# 3_6.net
KiCad netlist of a schematic drawn in Altium Designer
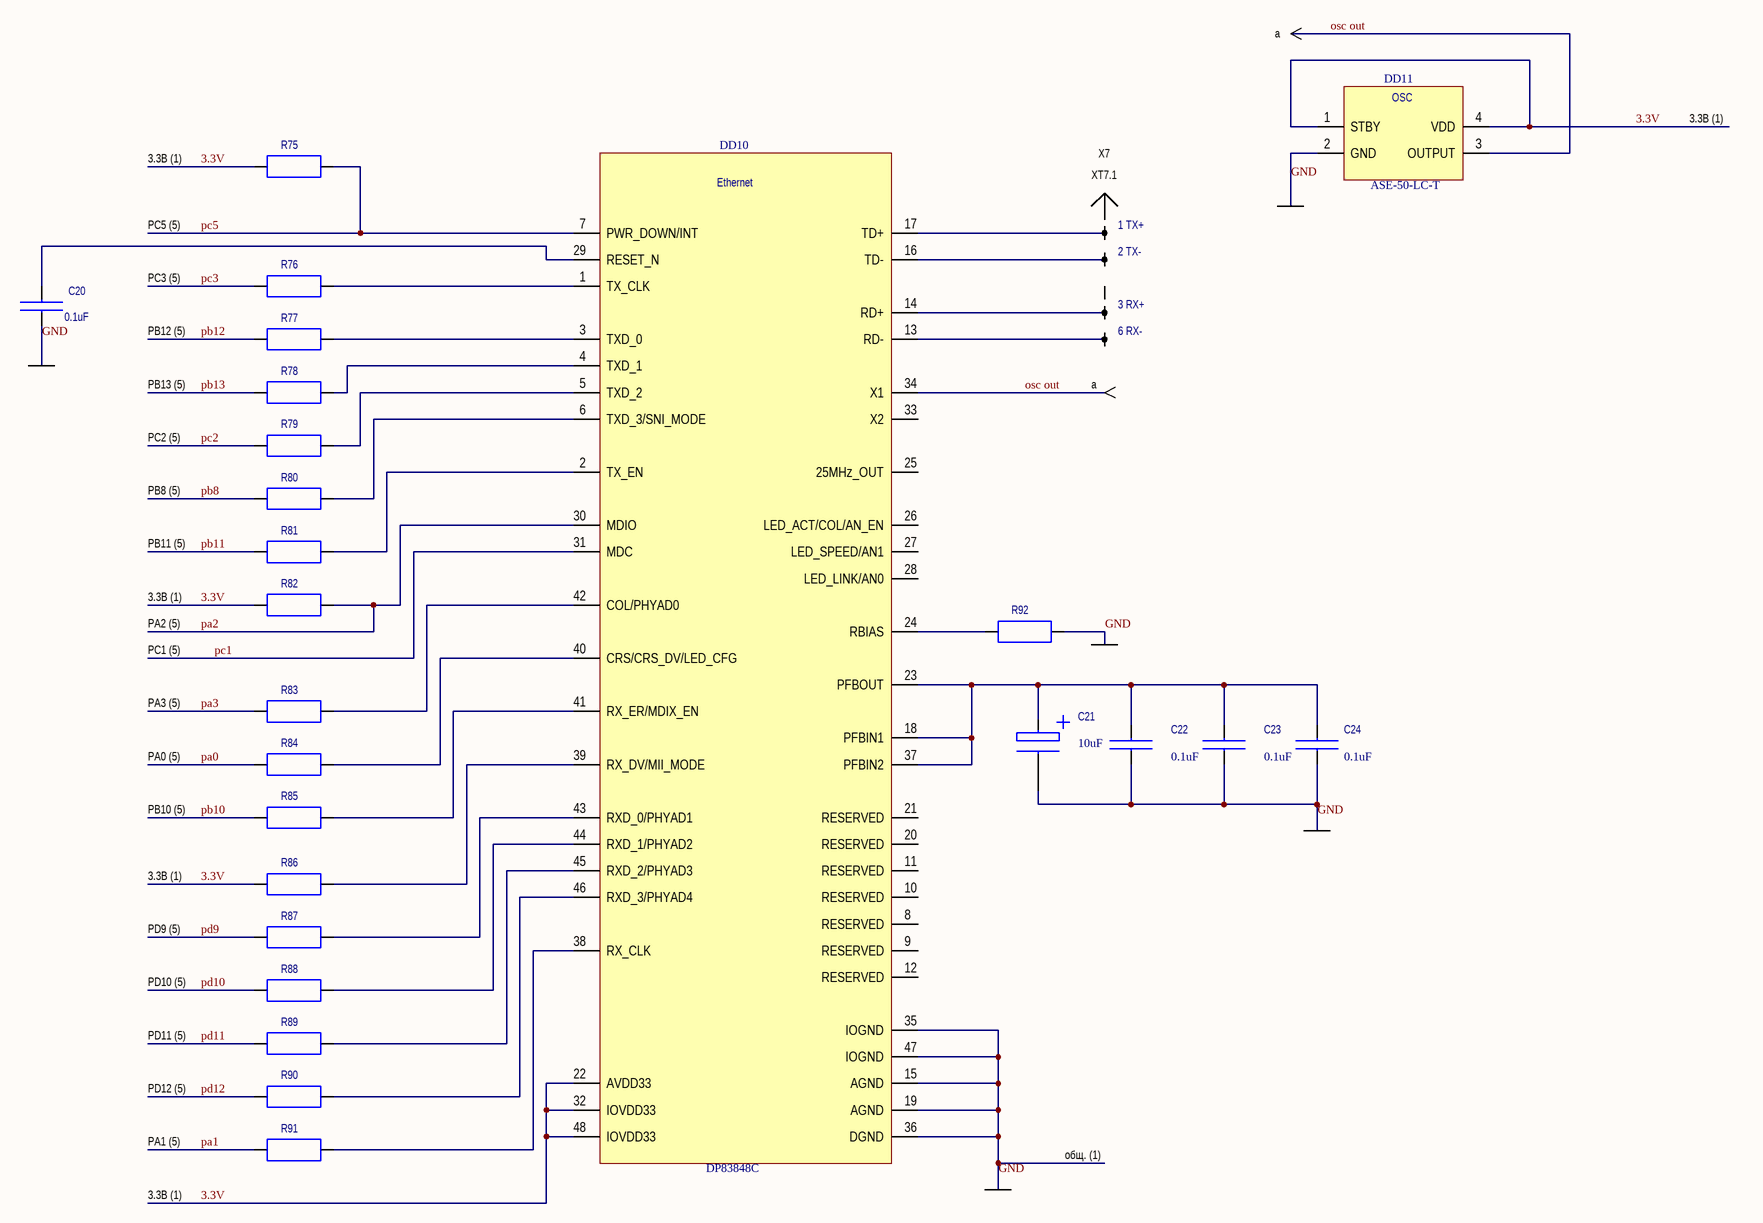
[diagram p0: Э3_6.SchDoc]

(export (version "E")
  (design (tool "Eeschema 10.0.6"))
  (components
    (comp (ref "C20") (value "0.1uF") (footprint "PcbLib1:CAP0805") (libsource (lib "Schlib1") (part "C")))
    (comp (ref "C21") (value "10uF") (footprint "PcbLib1:CAPT") (libsource (lib "Schlib1") (part "CL")))
    (comp (ref "C22") (value "0.1uF") (footprint "PcbLib1:CAP0805") (libsource (lib "Schlib1") (part "C")))
    (comp (ref "C23") (value "0.1uF") (libsource (lib "Schlib1") (part "C_2")))
    (comp (ref "C24") (value "0.1uF") (libsource (lib "Schlib1") (part "C_2")))
    (comp (ref "DD10")
      (value "DP83848C")
      (footprint "PcbLib1:VBH48A_N")
      (libsource (lib "Schlib1") (part "DP83848C"))
    )
    (comp (ref "DD11")
      (value "ASE-50-LC-T")
      (footprint "PcbLib1:ASE_OSC")
      (libsource (lib "Schlib1") (part "ASE-50-LC-T"))
    )
    (comp (ref "R75") (value "2.2k") (footprint "PcbLib1:RES0805") (libsource (lib "Schlib1") (part "R")))
    (comp (ref "R76") (value "51") (footprint "PcbLib1:RES0805") (libsource (lib "Schlib1") (part "R")))
    (comp (ref "R77") (value "51") (footprint "PcbLib1:RES0805") (libsource (lib "Schlib1") (part "R")))
    (comp (ref "R78") (value "51") (footprint "PcbLib1:RES0805") (libsource (lib "Schlib1") (part "R")))
    (comp (ref "R79") (value "51") (footprint "PcbLib1:RES0805") (libsource (lib "Schlib1") (part "R")))
    (comp (ref "R80") (value "51") (footprint "PcbLib1:RES0805") (libsource (lib "Schlib1") (part "R")))
    (comp (ref "R81") (value "51") (footprint "PcbLib1:RES0805") (libsource (lib "Schlib1") (part "R")))
    (comp (ref "R82") (value "1.5k") (footprint "PcbLib1:RES0805") (libsource (lib "Schlib1") (part "R")))
    (comp (ref "R83") (value "51") (footprint "PcbLib1:RES0805") (libsource (lib "Schlib1") (part "R")))
    (comp (ref "R84") (value "51") (footprint "PcbLib1:RES0805") (libsource (lib "Schlib1") (part "R")))
    (comp (ref "R85") (value "51") (footprint "PcbLib1:RES0805") (libsource (lib "Schlib1") (part "R")))
    (comp (ref "R86") (value "2.2k") (footprint "PcbLib1:RES0805") (libsource (lib "Schlib1") (part "R")))
    (comp (ref "R87") (value "51") (footprint "PcbLib1:RES0805") (libsource (lib "Schlib1") (part "R")))
    (comp (ref "R88") (value "51") (footprint "PcbLib1:RES0805") (libsource (lib "Schlib1") (part "R")))
    (comp (ref "R89") (value "51") (footprint "PcbLib1:RES0805") (libsource (lib "Schlib1") (part "R")))
    (comp (ref "R90") (value "51") (footprint "PcbLib1:RES0805") (libsource (lib "Schlib1") (part "R")))
    (comp (ref "R91") (value "51") (footprint "PcbLib1:RES0805") (libsource (lib "Schlib1") (part "R")))
    (comp (ref "R92") (value "4.87k") (libsource (lib "Schlib1") (part "R_1")))
    (comp (ref "X7") (value "1 TX+") (footprint "PcbLib1:RJ45") (libsource (lib "Schlib1") (part "RJ45")))
  )
  (nets
    (net (code "1") (name "/3.3V") (class "Default")
      (node (ref "DD10") (pin "22") (pinfunction "AVDD33_22") (pintype "passive"))
      (node (ref "DD10") (pin "32") (pinfunction "IOVDD33_32") (pintype "passive"))
      (node (ref "DD10") (pin "48") (pinfunction "IOVDD33_48") (pintype "passive"))
      (node (ref "DD11") (pin "1") (pinfunction "STBY_1") (pintype "passive"))
      (node (ref "DD11") (pin "4") (pinfunction "VDD_4") (pintype "passive"))
      (node (ref "R75") (pin "1") (pintype "passive"))
      (node (ref "R82") (pin "1") (pintype "passive"))
      (node (ref "R86") (pin "1") (pintype "passive"))
    )
    (net (code "2") (name "/GND") (class "Default")
      (node (ref "C20") (pin "1") (pintype "passive"))
      (node (ref "C22") (pin "1") (pintype "passive"))
      (node (ref "C23") (pin "1") (pintype "passive"))
      (node (ref "C24") (pin "1") (pintype "passive"))
      (node (ref "DD10") (pin "15") (pinfunction "AGND_15") (pintype "passive"))
      (node (ref "DD10") (pin "19") (pinfunction "AGND_19") (pintype "passive"))
      (node (ref "DD10") (pin "35") (pinfunction "IOGND_35") (pintype "passive"))
      (node (ref "DD10") (pin "36") (pinfunction "DGND_36") (pintype "passive"))
      (node (ref "DD10") (pin "47") (pinfunction "IOGND_47") (pintype "passive"))
      (node (ref "DD11") (pin "2") (pinfunction "GND_2") (pintype "passive"))
      (node (ref "R92") (pin "2") (pintype "passive"))
    )
    (net (code "3") (name "/osc out") (class "Default")
      (node (ref "DD10") (pin "34") (pinfunction "X1_34") (pintype "passive"))
      (node (ref "DD11") (pin "3") (pinfunction "OUTPUT_3") (pintype "passive"))
    )
    (net (code "4") (name "/pa0") (class "Default") (node (ref "R84") (pin "1") (pintype "passive")))
    (net (code "5") (name "/pa1") (class "Default") (node (ref "R91") (pin "1") (pintype "passive")))
    (net (code "6") (name "/pa2") (class "Default")
      (node (ref "DD10") (pin "30") (pinfunction "MDIO_30") (pintype "passive"))
      (node (ref "R82") (pin "2") (pintype "passive"))
    )
    (net (code "7") (name "/pa3") (class "Default") (node (ref "R83") (pin "1") (pintype "passive")))
    (net (code "8") (name "/pb8") (class "Default") (node (ref "R80") (pin "1") (pintype "passive")))
    (net (code "9") (name "/pb10") (class "Default") (node (ref "R85") (pin "1") (pintype "passive")))
    (net (code "10") (name "/pb11") (class "Default") (node (ref "R81") (pin "1") (pintype "passive")))
    (net (code "11") (name "/pb12") (class "Default") (node (ref "R77") (pin "1") (pintype "passive")))
    (net (code "12") (name "/pb13") (class "Default") (node (ref "R78") (pin "1") (pintype "passive")))
    (net (code "13") (name "/pc1") (class "Default")
      (node (ref "DD10") (pin "31") (pinfunction "MDC_31") (pintype "passive"))
    )
    (net (code "14") (name "/pc2") (class "Default") (node (ref "R79") (pin "1") (pintype "passive")))
    (net (code "15") (name "/pc3") (class "Default") (node (ref "R76") (pin "1") (pintype "passive")))
    (net (code "16") (name "/pc5") (class "Default")
      (node (ref "DD10") (pin "7") (pinfunction "PWR_DOWN/INT_7") (pintype "passive"))
      (node (ref "R75") (pin "2") (pintype "passive"))
    )
    (net (code "17") (name "/pd9") (class "Default") (node (ref "R87") (pin "1") (pintype "passive")))
    (net (code "18") (name "/pd10") (class "Default") (node (ref "R88") (pin "1") (pintype "passive")))
    (net (code "19") (name "/pd11") (class "Default") (node (ref "R89") (pin "1") (pintype "passive")))
    (net (code "20") (name "/pd12") (class "Default") (node (ref "R90") (pin "1") (pintype "passive")))
    (net (code "21") (name "Net-(DD10-COL{slash}PHYAD0)") (class "Default")
      (node (ref "DD10") (pin "42") (pinfunction "COL/PHYAD0_42") (pintype "passive"))
      (node (ref "R83") (pin "2") (pintype "passive"))
    )
    (net (code "22") (name "Net-(DD10-CRS{slash}CRS_DV{slash}LED_CFG)") (class "Default")
      (node (ref "DD10") (pin "40") (pinfunction "CRS/CRS_DV/LED_CFG_40") (pintype "passive"))
      (node (ref "R84") (pin "2") (pintype "passive"))
    )
    (net (code "23") (name "Net-(DD10-PFBIN1)") (class "Default")
      (node (ref "C21") (pin "1") (pintype "passive"))
      (node (ref "C22") (pin "2") (pintype "passive"))
      (node (ref "C23") (pin "2") (pintype "passive"))
      (node (ref "C24") (pin "2") (pintype "passive"))
      (node (ref "DD10") (pin "18") (pinfunction "PFBIN1_18") (pintype "passive"))
      (node (ref "DD10") (pin "23") (pinfunction "PFBOUT_23") (pintype "passive"))
      (node (ref "DD10") (pin "37") (pinfunction "PFBIN2_37") (pintype "passive"))
    )
    (net (code "24") (name "Net-(DD10-RBIAS)") (class "Default")
      (node (ref "DD10") (pin "24") (pinfunction "RBIAS_24") (pintype "passive"))
      (node (ref "R92") (pin "1") (pintype "passive"))
    )
    (net (code "25") (name "Net-(DD10-RD+)") (class "Default")
      (node (ref "DD10") (pin "14") (pinfunction "RD+_14") (pintype "passive"))
      (node (ref "X7") (pin "3") (pinfunction "1_3") (pintype "passive"))
    )
    (net (code "26") (name "Net-(DD10-RD-)") (class "Default")
      (node (ref "DD10") (pin "13") (pinfunction "RD-_13") (pintype "passive"))
      (node (ref "X7") (pin "6") (pinfunction "1_6") (pintype "passive"))
    )
    (net (code "27") (name "Net-(DD10-RESET_N)") (class "Default")
      (node (ref "C20") (pin "2") (pintype "passive"))
      (node (ref "DD10") (pin "29") (pinfunction "RESET_N_29") (pintype "passive"))
    )
    (net (code "28") (name "Net-(DD10-RXD_0{slash}PHYAD1)") (class "Default")
      (node (ref "DD10") (pin "43") (pinfunction "RXD_0/PHYAD1_43") (pintype "passive"))
      (node (ref "R87") (pin "2") (pintype "passive"))
    )
    (net (code "29") (name "Net-(DD10-RXD_1{slash}PHYAD2)") (class "Default")
      (node (ref "DD10") (pin "44") (pinfunction "RXD_1/PHYAD2_44") (pintype "passive"))
      (node (ref "R88") (pin "2") (pintype "passive"))
    )
    (net (code "30") (name "Net-(DD10-RXD_2{slash}PHYAD3)") (class "Default")
      (node (ref "DD10") (pin "45") (pinfunction "RXD_2/PHYAD3_45") (pintype "passive"))
      (node (ref "R89") (pin "2") (pintype "passive"))
    )
    (net (code "31") (name "Net-(DD10-RXD_3{slash}PHYAD4)") (class "Default")
      (node (ref "DD10") (pin "46") (pinfunction "RXD_3/PHYAD4_46") (pintype "passive"))
      (node (ref "R90") (pin "2") (pintype "passive"))
    )
    (net (code "32") (name "Net-(DD10-RX_CLK)") (class "Default")
      (node (ref "DD10") (pin "38") (pinfunction "RX_CLK_38") (pintype "passive"))
      (node (ref "R91") (pin "2") (pintype "passive"))
    )
    (net (code "33") (name "Net-(DD10-RX_DV{slash}MII_MODE)") (class "Default")
      (node (ref "DD10") (pin "39") (pinfunction "RX_DV/MII_MODE_39") (pintype "passive"))
      (node (ref "R86") (pin "2") (pintype "passive"))
    )
    (net (code "34") (name "Net-(DD10-RX_ER{slash}MDIX_EN)") (class "Default")
      (node (ref "DD10") (pin "41") (pinfunction "RX_ER/MDIX_EN_41") (pintype "passive"))
      (node (ref "R85") (pin "2") (pintype "passive"))
    )
    (net (code "35") (name "Net-(DD10-TD+)") (class "Default")
      (node (ref "DD10") (pin "17") (pinfunction "TD+_17") (pintype "passive"))
      (node (ref "X7") (pin "1") (pinfunction "1_1") (pintype "passive"))
    )
    (net (code "36") (name "Net-(DD10-TD-)") (class "Default")
      (node (ref "DD10") (pin "16") (pinfunction "TD-_16") (pintype "passive"))
      (node (ref "X7") (pin "2") (pinfunction "1_2") (pintype "passive"))
    )
    (net (code "37") (name "Net-(DD10-TXD_0)") (class "Default")
      (node (ref "DD10") (pin "3") (pinfunction "TXD_0_3") (pintype "passive"))
      (node (ref "R77") (pin "2") (pintype "passive"))
    )
    (net (code "38") (name "Net-(DD10-TXD_1)") (class "Default")
      (node (ref "DD10") (pin "4") (pinfunction "TXD_1_4") (pintype "passive"))
      (node (ref "R78") (pin "2") (pintype "passive"))
    )
    (net (code "39") (name "Net-(DD10-TXD_2)") (class "Default")
      (node (ref "DD10") (pin "5") (pinfunction "TXD_2_5") (pintype "passive"))
      (node (ref "R79") (pin "2") (pintype "passive"))
    )
    (net (code "40") (name "Net-(DD10-TXD_3{slash}SNI_MODE)") (class "Default")
      (node (ref "DD10") (pin "6") (pinfunction "TXD_3/SNI_MODE_6") (pintype "passive"))
      (node (ref "R80") (pin "2") (pintype "passive"))
    )
    (net (code "41") (name "Net-(DD10-TX_CLK)") (class "Default")
      (node (ref "DD10") (pin "1") (pinfunction "TX_CLK_1") (pintype "passive"))
      (node (ref "R76") (pin "2") (pintype "passive"))
    )
    (net (code "42") (name "Net-(DD10-TX_EN)") (class "Default")
      (node (ref "DD10") (pin "2") (pinfunction "TX_EN_2") (pintype "passive"))
      (node (ref "R81") (pin "2") (pintype "passive"))
    )
    (net (code "43") (name "unconnected-(C21-Pad2)") (class "Default")
      (node (ref "C21") (pin "2") (pintype "passive"))
    )
    (net (code "44") (name "unconnected-(DD10-25MHz_OUT-Pad25)") (class "Default")
      (node (ref "DD10") (pin "25") (pinfunction "25MHz_OUT_25") (pintype "passive"))
    )
    (net (code "45") (name "unconnected-(DD10-LED_ACT{slash}COL{slash}AN_EN-Pad26)") (class "Default")
      (node (ref "DD10") (pin "26") (pinfunction "LED_ACT/COL/AN_EN_26") (pintype "passive"))
    )
    (net (code "46") (name "unconnected-(DD10-LED_LINK{slash}AN0-Pad28)") (class "Default")
      (node (ref "DD10") (pin "28") (pinfunction "LED_LINK/AN0_28") (pintype "passive"))
    )
    (net (code "47") (name "unconnected-(DD10-LED_SPEED{slash}AN1-Pad27)") (class "Default")
      (node (ref "DD10") (pin "27") (pinfunction "LED_SPEED/AN1_27") (pintype "passive"))
    )
    (net (code "48") (name "unconnected-(DD10-RESERVED-Pad8)") (class "Default")
      (node (ref "DD10") (pin "8") (pinfunction "RESERVED_8") (pintype "passive"))
    )
    (net (code "49") (name "unconnected-(DD10-RESERVED-Pad9)") (class "Default")
      (node (ref "DD10") (pin "9") (pinfunction "RESERVED_9") (pintype "passive"))
    )
    (net (code "50") (name "unconnected-(DD10-RESERVED-Pad10)") (class "Default")
      (node (ref "DD10") (pin "10") (pinfunction "RESERVED_10") (pintype "passive"))
    )
    (net (code "51") (name "unconnected-(DD10-RESERVED-Pad11)") (class "Default")
      (node (ref "DD10") (pin "11") (pinfunction "RESERVED_11") (pintype "passive"))
    )
    (net (code "52") (name "unconnected-(DD10-RESERVED-Pad12)") (class "Default")
      (node (ref "DD10") (pin "12") (pinfunction "RESERVED_12") (pintype "passive"))
    )
    (net (code "53") (name "unconnected-(DD10-RESERVED-Pad20)") (class "Default")
      (node (ref "DD10") (pin "20") (pinfunction "RESERVED_20") (pintype "passive"))
    )
    (net (code "54") (name "unconnected-(DD10-RESERVED-Pad21)") (class "Default")
      (node (ref "DD10") (pin "21") (pinfunction "RESERVED_21") (pintype "passive"))
    )
    (net (code "55") (name "unconnected-(DD10-X2-Pad33)") (class "Default")
      (node (ref "DD10") (pin "33") (pinfunction "X2_33") (pintype "passive"))
    )
  )
)
